# 04-_Sub_Power_Supply.net
KiCad netlist of a schematic drawn in Altium Designer
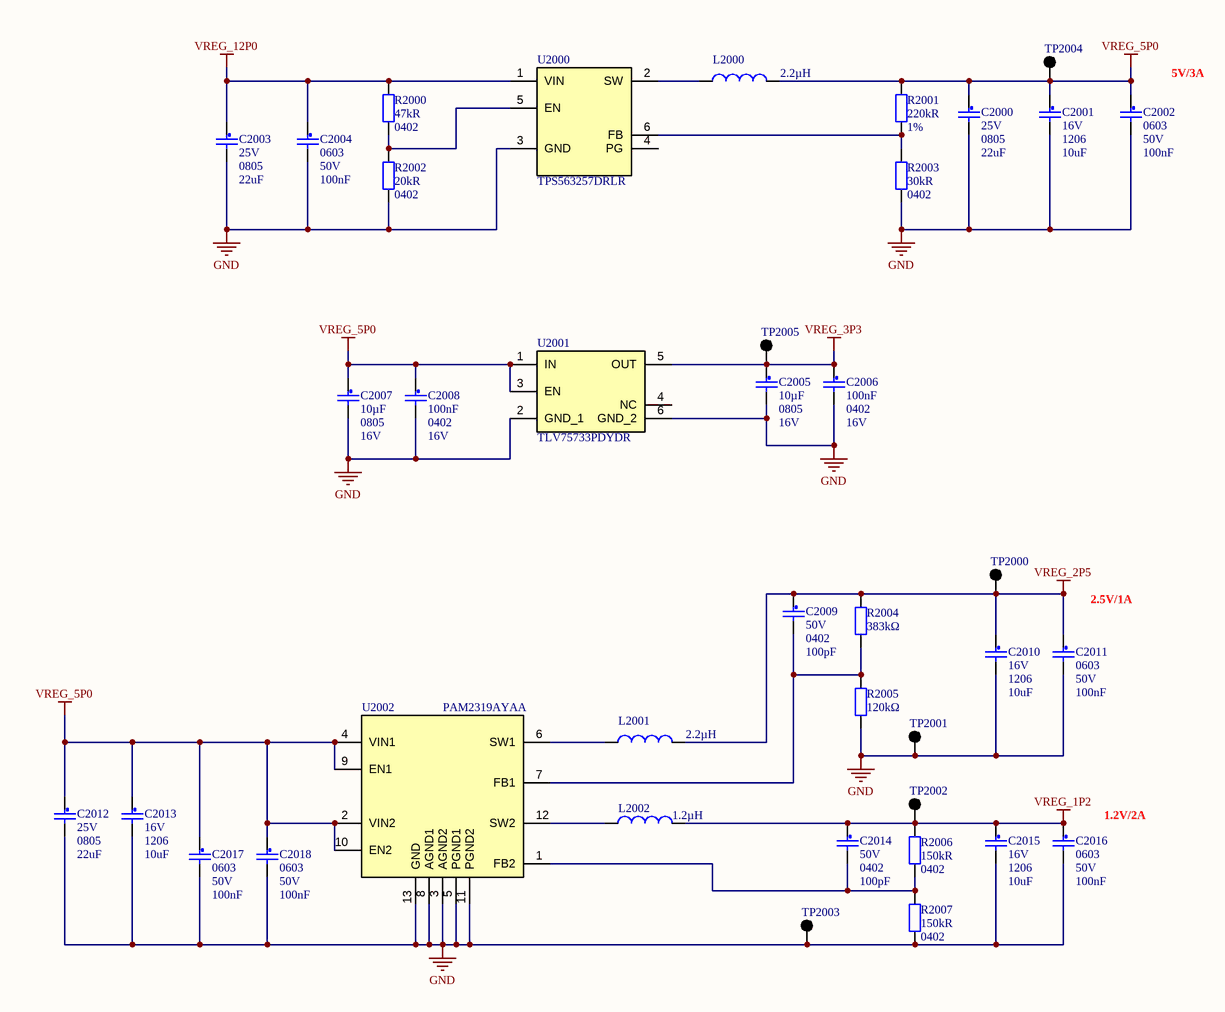
[diagram p0: 04- Sub Power Supply.SchDoc]

(export (version "E")
  (design (tool "Eeschema 10.0.6"))
  (components
    (comp (ref "C2000")
      (value "GRM21BR61E226ME44K")
      (footprint "CAP0805")
      (description "CAP CER 22uF 25V 20% X5R 0805 SMD")
      (fields
        (field (name "TOLERANCE") "20%")
        (field (name "VOLTAGE RATING") "25V")
        (field (name "CASE/PACKAGE") "0805")
        (field (name "CAPACITANCE") "22uF")
      )
      (libsource (lib "VMO_Lib") (part "CMP-ROOT-0068-6"))
    )
    (comp (ref "C2001")
      (value "CL31B106KOHVPNE")
      (footprint "CAP1206")
      (description "CAP CER 10uF 16V 10% X7R 1206 SMD")
      (fields
        (field (name "TOLERANCE") "10%")
        (field (name "VOLTAGE RATING") "16V")
        (field (name "CASE/PACKAGE") "1206")
        (field (name "CAPACITANCE") "10uF")
      )
      (libsource (lib "VMO_Lib") (part "CMP-00045-5"))
    )
    (comp (ref "C2002")
      (value "CL10B104KB8WPNC")
      (footprint "CAP0603")
      (description "CAP CER 0.1UF 50V X7R 0603")
      (fields
        (field (name "TOLERANCE") "10%")
        (field (name "CASE/PACKAGE") "0603")
        (field (name "VOLTAGE RATING") "50V")
        (field (name "CAPACITANCE") "100nF")
      )
      (libsource (lib "VMO_Lib") (part "CMP-00005-5"))
    )
    (comp (ref "C2003")
      (value "GRM21BR61E226ME44K")
      (footprint "CAP0805")
      (description "CAP CER 22uF 25V 20% X5R 0805 SMD")
      (fields
        (field (name "TOLERANCE") "20%")
        (field (name "VOLTAGE RATING") "25V")
        (field (name "CASE/PACKAGE") "0805")
        (field (name "CAPACITANCE") "22uF")
      )
      (libsource (lib "VMO_Lib") (part "CMP-ROOT-0068-6"))
    )
    (comp (ref "C2004")
      (value "CL10B104KB8WPNC")
      (footprint "CAP0603")
      (description "CAP CER 0.1UF 50V X7R 0603")
      (fields
        (field (name "TOLERANCE") "10%")
        (field (name "CASE/PACKAGE") "0603")
        (field (name "VOLTAGE RATING") "50V")
        (field (name "CAPACITANCE") "100nF")
      )
      (libsource (lib "VMO_Lib") (part "CMP-00005-5"))
    )
    (comp (ref "C2005")
      (value "10µF")
      (footprint "CAP0805")
      (description "CAP CER 10UF 16V X7R 0805")
      (fields
        (field (name "CASE/PACKAGE") "0805")
        (field (name "MANUFACTURER") "Murata")
        (field (name "MANUFACTURER PART NUMBER") "GRM21BZ71C106KE15L")
        (field (name "VOLTAGE RATING") "16V")
      )
      (libsource (lib "VMO_Lib") (part "CMP-01170-1"))
    )
    (comp (ref "C2006")
      (value "0402YC104KAT2A")
      (footprint "CAP0402")
      (description "CAP CER 0.1UF 16V X7R 0402")
      (fields
        (field (name "CAPACITANCE") "100nF")
        (field (name "CASE/PACKAGE") "0402")
        (field (name "VOLTAGE RATING (DC)") "16V")
      )
      (libsource (lib "VMO_Lib") (part "CMP-00988-1"))
    )
    (comp (ref "C2007")
      (value "10µF")
      (footprint "CAP0805")
      (description "CAP CER 10UF 16V X7R 0805")
      (fields
        (field (name "CASE/PACKAGE") "0805")
        (field (name "MANUFACTURER") "Murata")
        (field (name "MANUFACTURER PART NUMBER") "GRM21BZ71C106KE15L")
        (field (name "VOLTAGE RATING") "16V")
      )
      (libsource (lib "VMO_Lib") (part "CMP-01170-1"))
    )
    (comp (ref "C2008")
      (value "0402YC104KAT2A")
      (footprint "CAP0402")
      (description "CAP CER 0.1UF 16V X7R 0402")
      (fields
        (field (name "CAPACITANCE") "100nF")
        (field (name "CASE/PACKAGE") "0402")
        (field (name "VOLTAGE RATING (DC)") "16V")
      )
      (libsource (lib "VMO_Lib") (part "CMP-00988-1"))
    )
    (comp (ref "C2009")
      (value "GCM1555C1H101JA16D")
      (footprint "CAP0402")
      (description "CAP CER 100pF 50V 5% C0G 0402 SMD")
      (fields
        (field (name "VOLTAGE") "50V")
        (field (name "TOLERANCE") "5%")
        (field (name "VOLTAGE RATING") "50V")
        (field (name "CASE/PACKAGE") "0402")
        (field (name "CAPACITANCE") "100pF")
      )
      (libsource (lib "VMO_Lib") (part "CMP-00107-4"))
    )
    (comp (ref "C2010")
      (value "CL31B106KOHVPNE")
      (footprint "CAP1206")
      (description "CAP CER 10uF 16V 10% X7R 1206 SMD")
      (fields
        (field (name "TOLERANCE") "10%")
        (field (name "VOLTAGE RATING") "16V")
        (field (name "CASE/PACKAGE") "1206")
        (field (name "CAPACITANCE") "10uF")
      )
      (libsource (lib "VMO_Lib") (part "CMP-00045-5"))
    )
    (comp (ref "C2011")
      (value "CL10B104KB8WPNC")
      (footprint "CAP0603")
      (description "CAP CER 0.1UF 50V X7R 0603")
      (fields
        (field (name "TOLERANCE") "10%")
        (field (name "CASE/PACKAGE") "0603")
        (field (name "VOLTAGE RATING") "50V")
        (field (name "CAPACITANCE") "100nF")
      )
      (libsource (lib "VMO_Lib") (part "CMP-00005-5"))
    )
    (comp (ref "C2012")
      (value "GRM21BR61E226ME44K")
      (footprint "CAP0805")
      (description "CAP CER 22uF 25V 20% X5R 0805 SMD")
      (fields
        (field (name "TOLERANCE") "20%")
        (field (name "VOLTAGE RATING") "25V")
        (field (name "CASE/PACKAGE") "0805")
        (field (name "CAPACITANCE") "22uF")
      )
      (libsource (lib "VMO_Lib") (part "CMP-ROOT-0068-6"))
    )
    (comp (ref "C2013")
      (value "CL31B106KOHVPNE")
      (footprint "CAP1206")
      (description "CAP CER 10uF 16V 10% X7R 1206 SMD")
      (fields
        (field (name "TOLERANCE") "10%")
        (field (name "VOLTAGE RATING") "16V")
        (field (name "CASE/PACKAGE") "1206")
        (field (name "CAPACITANCE") "10uF")
      )
      (libsource (lib "VMO_Lib") (part "CMP-00045-5"))
    )
    (comp (ref "C2014")
      (value "GCM1555C1H101JA16D")
      (footprint "CAP0402")
      (description "CAP CER 100pF 50V 5% C0G 0402 SMD")
      (fields
        (field (name "VOLTAGE") "50V")
        (field (name "TOLERANCE") "5%")
        (field (name "VOLTAGE RATING") "50V")
        (field (name "CASE/PACKAGE") "0402")
        (field (name "CAPACITANCE") "100pF")
      )
      (libsource (lib "VMO_Lib") (part "CMP-00107-4"))
    )
    (comp (ref "C2015")
      (value "CL31B106KOHVPNE")
      (footprint "CAP1206")
      (description "CAP CER 10uF 16V 10% X7R 1206 SMD")
      (fields
        (field (name "TOLERANCE") "10%")
        (field (name "VOLTAGE RATING") "16V")
        (field (name "CASE/PACKAGE") "1206")
        (field (name "CAPACITANCE") "10uF")
      )
      (libsource (lib "VMO_Lib") (part "CMP-00045-5"))
    )
    (comp (ref "C2016")
      (value "CL10B104KB8WPNC")
      (footprint "CAP0603")
      (description "CAP CER 0.1UF 50V X7R 0603")
      (fields
        (field (name "TOLERANCE") "10%")
        (field (name "CASE/PACKAGE") "0603")
        (field (name "VOLTAGE RATING") "50V")
        (field (name "CAPACITANCE") "100nF")
      )
      (libsource (lib "VMO_Lib") (part "CMP-00005-5"))
    )
    (comp (ref "C2017")
      (value "CL10B104KB8WPNC")
      (footprint "CAP0603")
      (description "CAP CER 0.1UF 50V X7R 0603")
      (fields
        (field (name "TOLERANCE") "10%")
        (field (name "CASE/PACKAGE") "0603")
        (field (name "VOLTAGE RATING") "50V")
        (field (name "CAPACITANCE") "100nF")
      )
      (libsource (lib "VMO_Lib") (part "CMP-00005-5"))
    )
    (comp (ref "C2018")
      (value "CL10B104KB8WPNC")
      (footprint "CAP0603")
      (description "CAP CER 0.1UF 50V X7R 0603")
      (fields
        (field (name "TOLERANCE") "10%")
        (field (name "CASE/PACKAGE") "0603")
        (field (name "VOLTAGE RATING") "50V")
        (field (name "CAPACITANCE") "100nF")
      )
      (libsource (lib "VMO_Lib") (part "CMP-00005-5"))
    )
    (comp (ref "L2000")
      (value "2.2µH")
      (footprint "INDP414121")
      (description "FIXED IND 2.2UH 4.7A 35 MOHM SMD")
      (fields
        (field (name "MANUFACTURER") "Wurth Elektronik")
        (field (name "MANUFACTURER PART NUMBER") "74438356022")
      )
      (libsource (lib "VMO_Lib") (part "CMP-01184-1"))
    )
    (comp (ref "L2001")
      (value "2.2µH")
      (footprint "INDP414121")
      (description "FIXED IND 2.2UH 4.7A 35 MOHM SMD")
      (fields
        (field (name "MANUFACTURER") "Wurth Elektronik")
        (field (name "MANUFACTURER PART NUMBER") "74438356022")
      )
      (libsource (lib "VMO_Lib") (part "CMP-01184-1"))
    )
    (comp (ref "L2002")
      (value "1.2µH")
      (footprint "INDP414121")
      (description "FIXED IND 1.2UH 5.8A 18 MOHM SMD")
      (fields
        (field (name "MANUFACTURER") "Wurth Elektronik")
        (field (name "MANUFACTURER PART NUMBER") "74438356012")
      )
      (libsource (lib "VMO_Lib") (part "CMP-01185-1"))
    )
    (comp (ref "R2000")
      (value "AC0402JR-0747KL")
      (footprint "RES0402")
      (description "RES SMD 47K OHM 5% 1/16W 0402")
      (fields
        (field (name "TOLERANCE") "5%")
        (field (name "RESISTANCE") "47kR")
        (field (name "CASE/PACKAGE") "0402")
      )
      (libsource (lib "VMO_Lib") (part "CMP-00109-2"))
    )
    (comp (ref "R2001")
      (value "220kR")
      (footprint "RES0603")
      (description "RES 220K OHM 1% 1/10W 0603")
      (fields
        (field (name "MANUFACTURER") "Stackpole Electronics")
        (field (name "MANUFACTURER PART NUMBER") "RMCF0603FT220K")
        (field (name "TOLERANCE") "1%")
      )
      (libsource (lib "VMO_Lib") (part "CMP-01087-1"))
    )
    (comp (ref "R2002")
      (value "RC0402FR-0720KL")
      (footprint "RES0402")
      (description "RES SMD 20K OHM 1% 1/16W 0402")
      (fields
        (field (name "TOLERANCE") "1%")
        (field (name "RESISTANCE") "20kR")
        (field (name "CASE/PACKAGE") "0402")
      )
      (libsource (lib "VMO_Lib") (part "CMP-00464-1"))
    )
    (comp (ref "R2003")
      (value "RMCF0402FT30K0")
      (footprint "RES0402")
      (description "RES 30kR 1/16W 1% 0402 SMD")
      (fields
        (field (name "TOLERANCE") "1%")
        (field (name "RESISTANCE") "30kR")
        (field (name "CASE/PACKAGE") "0402")
      )
      (libsource (lib "VMO_Lib") (part "CMP-00355-2"))
    )
    (comp (ref "R2004")
      (value "383kΩ")
      (footprint "RES0402")
      (description "RES 383K OHM 1% 1/16W 0402")
      (fields
        (field (name "MANUFACTURER") "Yageo Group")
        (field (name "MANUFACTURER PART NUMBER") "RC0402FR-07383KL")
      )
      (libsource (lib "VMO_Lib") (part "CMP-01187-1"))
    )
    (comp (ref "R2005")
      (value "120kΩ")
      (footprint "RES0402")
      (description "RES SMD 120K OHM 1% 1/16W 0402")
      (fields
        (field (name "MANUFACTURER") "Yageo Group")
        (field (name "MANUFACTURER PART NUMBER") "RT0402FRE07120KL")
      )
      (libsource (lib "VMO_Lib") (part "CMP-01186-1"))
    )
    (comp (ref "R2006")
      (value "RC0402FR-07150KL")
      (footprint "RES0402")
      (description "RES SMD 150K OHM 1% 1/16W 0402")
      (fields
        (field (name "TOLERANCE") "1%")
        (field (name "RESISTANCE") "150kR")
        (field (name "CASE/PACKAGE") "0402")
      )
      (libsource (lib "VMO_Lib") (part "CMP-00368-1"))
    )
    (comp (ref "R2007")
      (value "RC0402FR-07150KL")
      (footprint "RES0402")
      (description "RES SMD 150K OHM 1% 1/16W 0402")
      (fields
        (field (name "TOLERANCE") "1%")
        (field (name "RESISTANCE") "150kR")
        (field (name "CASE/PACKAGE") "0402")
      )
      (libsource (lib "VMO_Lib") (part "CMP-00368-1"))
    )
    (comp (ref "TP2000")
      (value "TP")
      (footprint "TP-SMD-R1")
      (description "Test Point 1x1mm")
      (libsource (lib "VMO_Lib") (part "CMP-ROOT-0080-12"))
    )
    (comp (ref "TP2001")
      (value "TP")
      (footprint "TP-SMD-R1")
      (description "Test Point 1x1mm")
      (libsource (lib "VMO_Lib") (part "CMP-ROOT-0080-12"))
    )
    (comp (ref "TP2002")
      (value "TP")
      (footprint "TP-SMD-R1")
      (description "Test Point 1x1mm")
      (libsource (lib "VMO_Lib") (part "CMP-ROOT-0080-12"))
    )
    (comp (ref "TP2003")
      (value "TP")
      (footprint "TP-SMD-R1")
      (description "Test Point 1x1mm")
      (libsource (lib "VMO_Lib") (part "CMP-ROOT-0080-12"))
    )
    (comp (ref "TP2004")
      (value "TP")
      (footprint "TP-SMD-R1")
      (description "Test Point 1x1mm")
      (libsource (lib "VMO_Lib") (part "CMP-ROOT-0080-12"))
    )
    (comp (ref "TP2005")
      (value "TP")
      (footprint "TP-SMD-R1")
      (description "Test Point 1x1mm")
      (libsource (lib "VMO_Lib") (part "CMP-ROOT-0080-12"))
    )
    (comp (ref "U2000")
      (value "TPS563257DRLR")
      (footprint "SOT-563")
      (description "IC REG BUCK ADJ 3A SOT563")
      (fields (field (name "MANUFACTURER") "Texas Instruments"))
      (libsource (lib "VMO_Lib") (part "CMP-01183-1"))
    )
    (comp (ref "U2001")
      (value "TLV75733PDYDR")
      (footprint "SOT-23-5 with EPAD")
      (description "IC REG LINEAR 3.3V 1A SOT23-5")
      (fields (field (name "MANUFACTURER") "Texas Instruments"))
      (libsource (lib "VMO_Lib") (part "CMP-01189-1"))
    )
    (comp (ref "U2002")
      (value "PAM2319AYAA")
      (footprint "12-WFDFN_Exposed Pad")
      (description "IC REG BUCK ADJ 1A/2A DL 12WDFN")
      (fields (field (name "MANUFACTURER") "Diodes Inc."))
      (libsource (lib "VMO_Lib") (part "CMP-01159-1"))
    )
  )
  (nets
    (net (code "1") (name "GND") (class "Default")
      (node (ref "C2000") (pin "2") (pinfunction "2_2") (pintype "passive"))
      (node (ref "C2001") (pin "2") (pinfunction "2_2") (pintype "passive"))
      (node (ref "C2002") (pin "2") (pinfunction "2_2") (pintype "passive"))
      (node (ref "C2003") (pin "2") (pinfunction "2_2") (pintype "passive"))
      (node (ref "C2004") (pin "2") (pinfunction "2_2") (pintype "passive"))
      (node (ref "C2005") (pin "2") (pinfunction "2_2") (pintype "passive"))
      (node (ref "C2006") (pin "2") (pinfunction "2_2") (pintype "passive"))
      (node (ref "C2007") (pin "2") (pinfunction "2_2") (pintype "passive"))
      (node (ref "C2008") (pin "2") (pinfunction "2_2") (pintype "passive"))
      (node (ref "C2010") (pin "2") (pinfunction "2_2") (pintype "passive"))
      (node (ref "C2011") (pin "2") (pinfunction "2_2") (pintype "passive"))
      (node (ref "C2012") (pin "2") (pinfunction "2_2") (pintype "passive"))
      (node (ref "C2013") (pin "2") (pinfunction "2_2") (pintype "passive"))
      (node (ref "C2015") (pin "2") (pinfunction "2_2") (pintype "passive"))
      (node (ref "C2016") (pin "2") (pinfunction "2_2") (pintype "passive"))
      (node (ref "C2017") (pin "2") (pinfunction "2_2") (pintype "passive"))
      (node (ref "C2018") (pin "2") (pinfunction "2_2") (pintype "passive"))
      (node (ref "R2002") (pin "1") (pinfunction "1_1") (pintype "passive"))
      (node (ref "R2003") (pin "1") (pinfunction "1_1") (pintype "passive"))
      (node (ref "R2005") (pin "1") (pinfunction "1_1") (pintype "passive"))
      (node (ref "R2007") (pin "1") (pinfunction "1_1") (pintype "passive"))
      (node (ref "TP2001") (pin "1") (pinfunction "1_1") (pintype "passive"))
      (node (ref "TP2003") (pin "1") (pinfunction "1_1") (pintype "passive"))
      (node (ref "U2000") (pin "3") (pinfunction "GND_3") (pintype "passive"))
      (node (ref "U2001") (pin "2") (pinfunction "GND_1_2") (pintype "passive"))
      (node (ref "U2001") (pin "6") (pinfunction "GND_2_6") (pintype "passive"))
      (node (ref "U2002") (pin "11") (pinfunction "PGND2_11") (pintype "passive"))
      (node (ref "U2002") (pin "13") (pinfunction "GND_13") (pintype "passive"))
      (node (ref "U2002") (pin "3") (pinfunction "AGND2_3") (pintype "passive"))
      (node (ref "U2002") (pin "5") (pinfunction "PGND1_5") (pintype "passive"))
      (node (ref "U2002") (pin "8") (pinfunction "AGND1_8") (pintype "passive"))
    )
    (net (code "2") (name "Net-(U2000-EN)") (class "Default")
      (node (ref "R2000") (pin "1") (pinfunction "1_1") (pintype "passive"))
      (node (ref "R2002") (pin "2") (pinfunction "2_2") (pintype "passive"))
      (node (ref "U2000") (pin "5") (pinfunction "EN_5") (pintype "passive"))
    )
    (net (code "3") (name "Net-(U2000-FB)") (class "Default")
      (node (ref "R2001") (pin "2") (pinfunction "2_2") (pintype "passive"))
      (node (ref "R2003") (pin "2") (pinfunction "2_2") (pintype "passive"))
      (node (ref "U2000") (pin "6") (pinfunction "FB_6") (pintype "passive"))
    )
    (net (code "4") (name "Net-(U2000-SW)") (class "Default")
      (node (ref "L2000") (pin "1") (pinfunction "1_1") (pintype "passive"))
      (node (ref "U2000") (pin "2") (pinfunction "SW_2") (pintype "passive"))
    )
    (net (code "5") (name "Net-(U2002-FB1)") (class "Default")
      (node (ref "C2009") (pin "2") (pinfunction "2_2") (pintype "passive"))
      (node (ref "R2004") (pin "1") (pinfunction "1_1") (pintype "passive"))
      (node (ref "R2005") (pin "2") (pinfunction "2_2") (pintype "passive"))
      (node (ref "U2002") (pin "7") (pinfunction "FB1_7") (pintype "passive"))
    )
    (net (code "6") (name "Net-(U2002-FB2)") (class "Default")
      (node (ref "C2014") (pin "2") (pinfunction "2_2") (pintype "passive"))
      (node (ref "R2006") (pin "1") (pinfunction "1_1") (pintype "passive"))
      (node (ref "R2007") (pin "2") (pinfunction "2_2") (pintype "passive"))
      (node (ref "U2002") (pin "1") (pinfunction "FB2_1") (pintype "passive"))
    )
    (net (code "7") (name "Net-(U2002-SW1)") (class "Default")
      (node (ref "L2001") (pin "1") (pinfunction "1_1") (pintype "passive"))
      (node (ref "U2002") (pin "6") (pinfunction "SW1_6") (pintype "passive"))
    )
    (net (code "8") (name "Net-(U2002-SW2)") (class "Default")
      (node (ref "L2002") (pin "1") (pinfunction "1_1") (pintype "passive"))
      (node (ref "U2002") (pin "12") (pinfunction "SW2_12") (pintype "passive"))
    )
    (net (code "9") (name "VREG_1P2") (class "Default")
      (node (ref "C2014") (pin "1") (pinfunction "1_1") (pintype "passive"))
      (node (ref "C2015") (pin "1") (pinfunction "1_1") (pintype "passive"))
      (node (ref "C2016") (pin "1") (pinfunction "1_1") (pintype "passive"))
      (node (ref "L2002") (pin "2") (pinfunction "2_2") (pintype "passive"))
      (node (ref "R2006") (pin "2") (pinfunction "2_2") (pintype "passive"))
      (node (ref "TP2002") (pin "1") (pinfunction "1_1") (pintype "passive"))
    )
    (net (code "10") (name "VREG_2P5") (class "Default")
      (node (ref "C2009") (pin "1") (pinfunction "1_1") (pintype "passive"))
      (node (ref "C2010") (pin "1") (pinfunction "1_1") (pintype "passive"))
      (node (ref "C2011") (pin "1") (pinfunction "1_1") (pintype "passive"))
      (node (ref "L2001") (pin "2") (pinfunction "2_2") (pintype "passive"))
      (node (ref "R2004") (pin "2") (pinfunction "2_2") (pintype "passive"))
      (node (ref "TP2000") (pin "1") (pinfunction "1_1") (pintype "passive"))
    )
    (net (code "11") (name "VREG_3P3") (class "Default")
      (node (ref "C2005") (pin "1") (pinfunction "1_1") (pintype "passive"))
      (node (ref "C2006") (pin "1") (pinfunction "1_1") (pintype "passive"))
      (node (ref "TP2005") (pin "1") (pinfunction "1_1") (pintype "passive"))
      (node (ref "U2001") (pin "5") (pinfunction "OUT_5") (pintype "passive"))
    )
    (net (code "12") (name "VREG_5P0") (class "Default")
      (node (ref "C2000") (pin "1") (pinfunction "1_1") (pintype "passive"))
      (node (ref "C2001") (pin "1") (pinfunction "1_1") (pintype "passive"))
      (node (ref "C2002") (pin "1") (pinfunction "1_1") (pintype "passive"))
      (node (ref "C2007") (pin "1") (pinfunction "1_1") (pintype "passive"))
      (node (ref "C2008") (pin "1") (pinfunction "1_1") (pintype "passive"))
      (node (ref "C2012") (pin "1") (pinfunction "1_1") (pintype "passive"))
      (node (ref "C2013") (pin "1") (pinfunction "1_1") (pintype "passive"))
      (node (ref "C2017") (pin "1") (pinfunction "1_1") (pintype "passive"))
      (node (ref "C2018") (pin "1") (pinfunction "1_1") (pintype "passive"))
      (node (ref "L2000") (pin "2") (pinfunction "2_2") (pintype "passive"))
      (node (ref "R2001") (pin "1") (pinfunction "1_1") (pintype "passive"))
      (node (ref "TP2004") (pin "1") (pinfunction "1_1") (pintype "passive"))
      (node (ref "U2001") (pin "1") (pinfunction "IN_1") (pintype "passive"))
      (node (ref "U2001") (pin "3") (pinfunction "EN_3") (pintype "passive"))
      (node (ref "U2002") (pin "10") (pinfunction "EN2_10") (pintype "passive"))
      (node (ref "U2002") (pin "2") (pinfunction "VIN2_2") (pintype "passive"))
      (node (ref "U2002") (pin "4") (pinfunction "VIN1_4") (pintype "passive"))
      (node (ref "U2002") (pin "9") (pinfunction "EN1_9") (pintype "passive"))
    )
    (net (code "13") (name "VREG_12P0") (class "Default")
      (node (ref "C2003") (pin "1") (pinfunction "1_1") (pintype "passive"))
      (node (ref "C2004") (pin "1") (pinfunction "1_1") (pintype "passive"))
      (node (ref "R2000") (pin "2") (pinfunction "2_2") (pintype "passive"))
      (node (ref "U2000") (pin "1") (pinfunction "VIN_1") (pintype "passive"))
    )
    (net (code "14") (name "unconnected-(U2000-PG-Pad4)") (class "Default")
      (node (ref "U2000") (pin "4") (pinfunction "PG_4") (pintype "passive"))
    )
    (net (code "15") (name "unconnected-(U2001-NC-Pad4)") (class "Default")
      (node (ref "U2001") (pin "4") (pinfunction "NC_4") (pintype "passive"))
    )
  )
)
